# CE842170047_SHEET5.net
KiCad netlist of a schematic drawn in Altium Designer
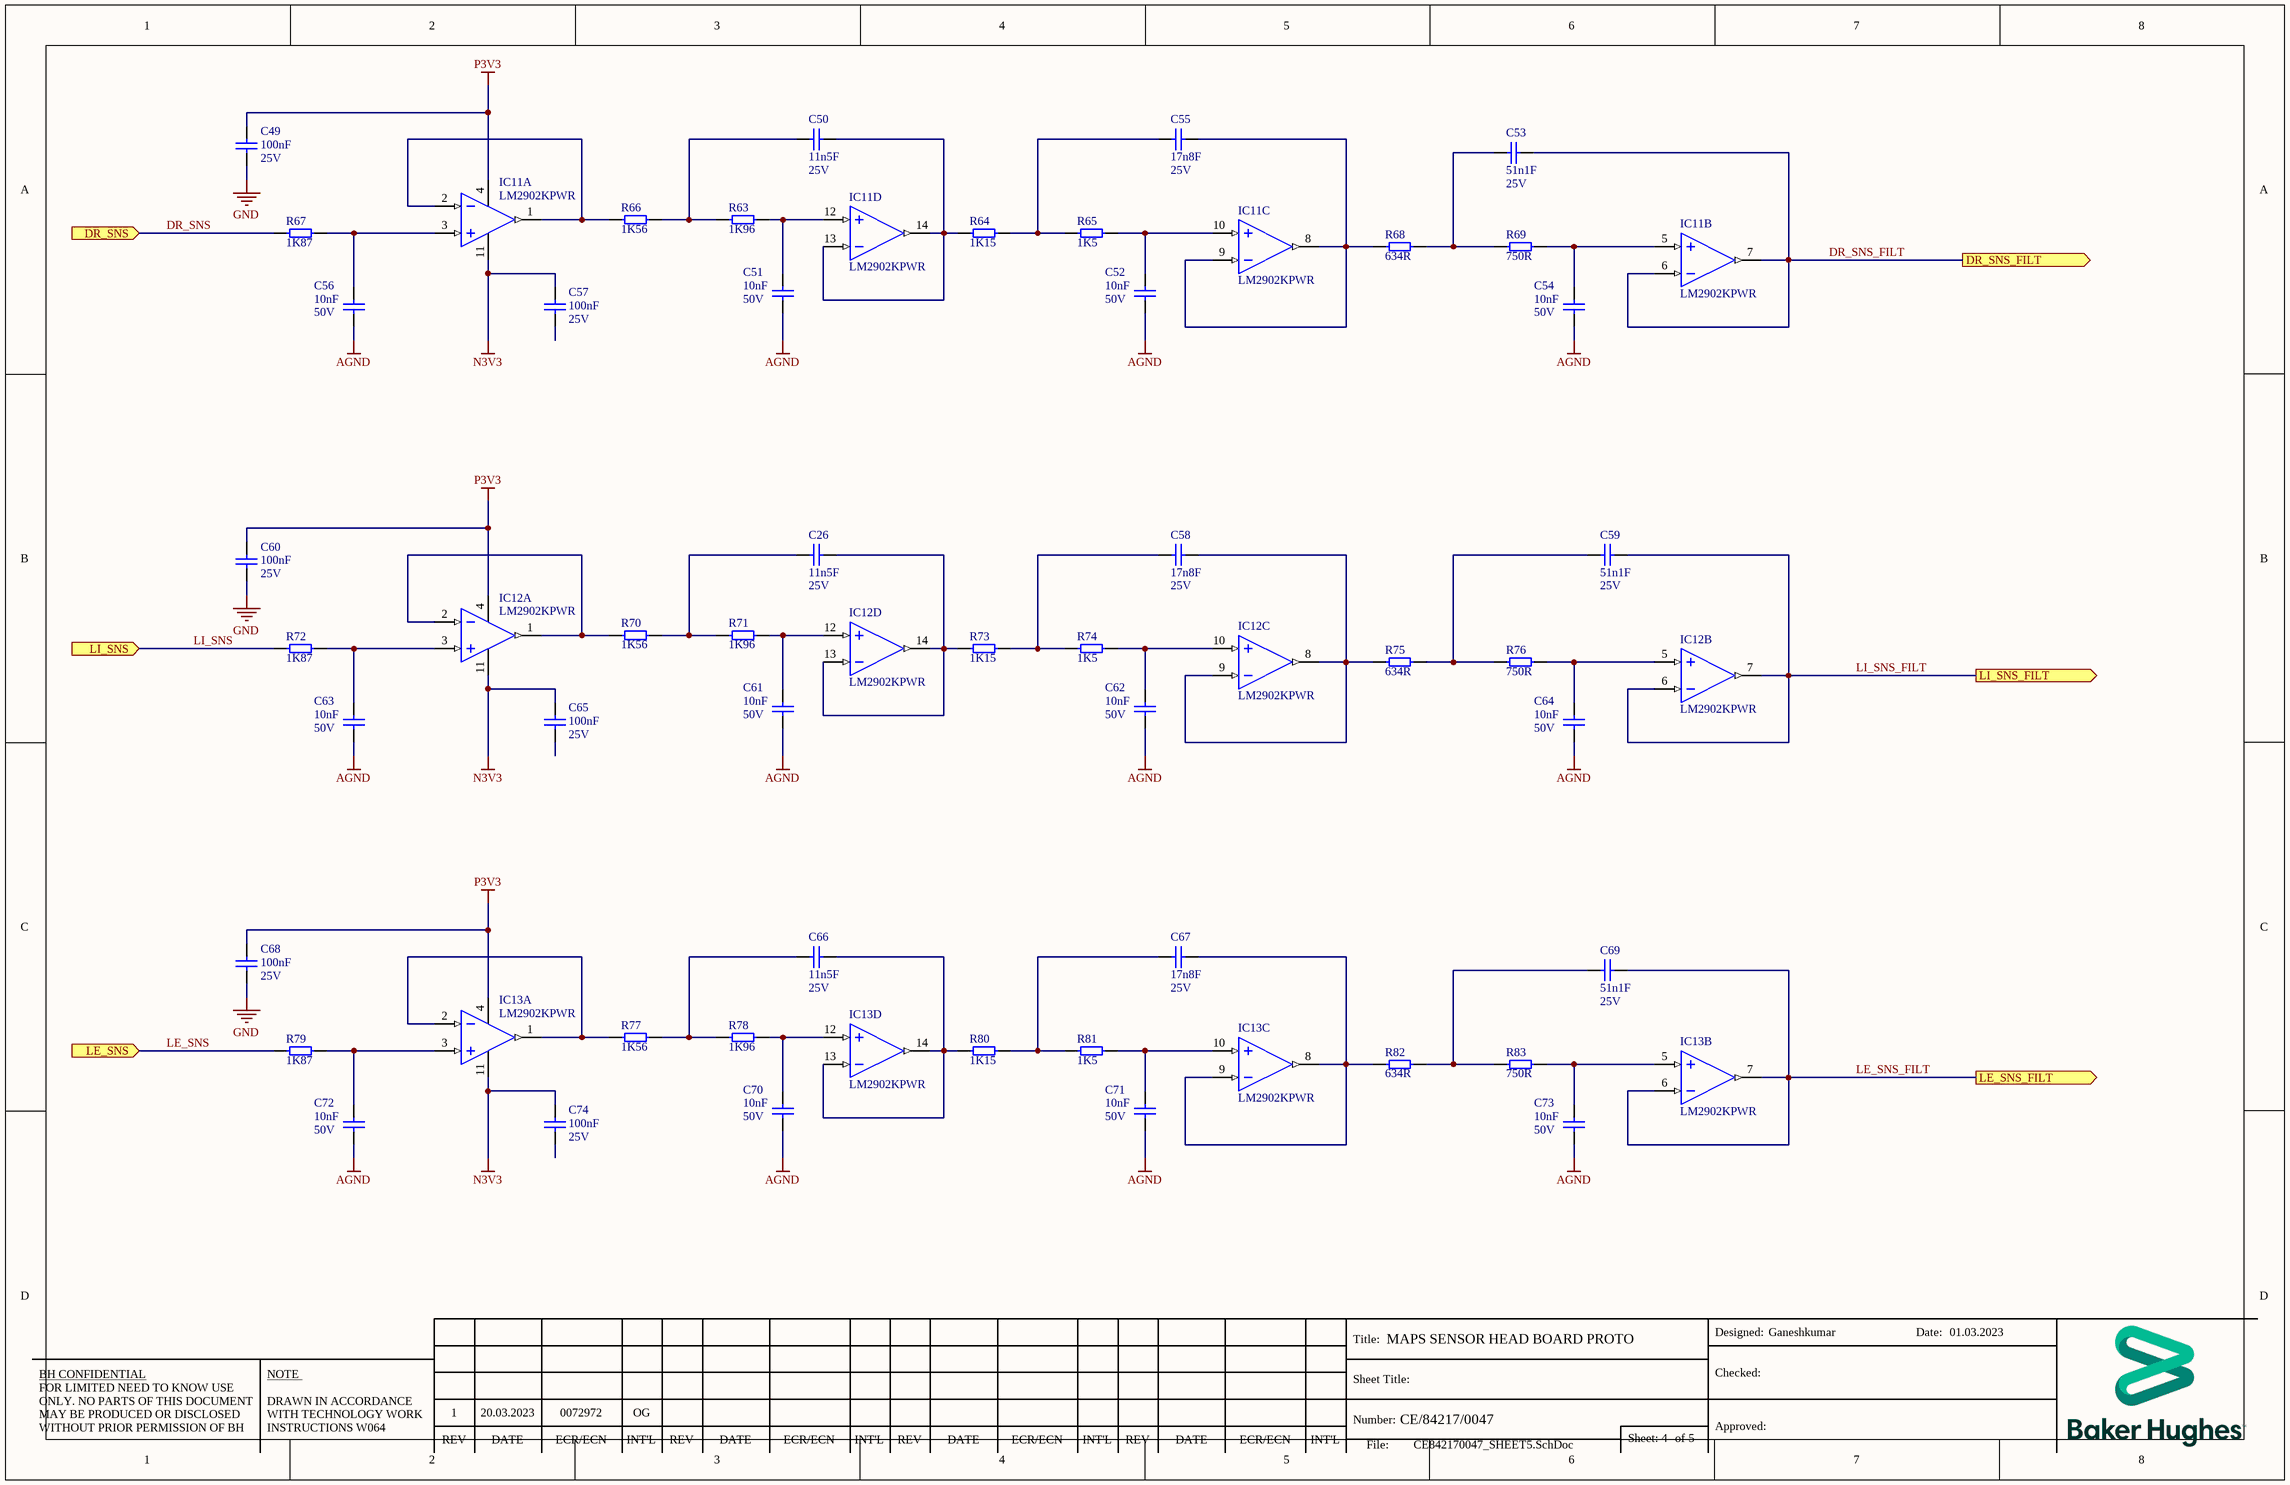
[diagram p0: CE842170047_SHEET5.SchDoc]

(export (version "E")
  (design (tool "Eeschema 10.0.6"))
  (components
    (comp (ref "C26")
      (value "11n5F")
      (footprint "C0603")
      (description "CAPACITOR CER 0603 11n5F 10% 25V X5R")
      (fields
        (field (name "VOLTAGE") "25V")
        (field (name "PII_PARTNUMBER") "KK/96159/0407")
        (field (name "TOLERANCE") "10%")
      )
      (libsource (lib "AltiumComponents") (part "CAP_GENERIC"))
    )
    (comp (ref "C49")
      (value "100nF")
      (footprint "C0603")
      (description "CAPACITOR_100nF_+10%_25V_603")
      (fields
        (field (name "VOLTAGE") "25V")
        (field (name "PII_PARTNUMBER") "KK/96159/4501")
        (field (name "TOLERANCE") "10%")
      )
      (libsource (lib "AltiumComponents") (part "CAP_GENERIC"))
    )
    (comp (ref "C50")
      (value "11n5F")
      (footprint "C0603")
      (description "CAPACITOR CER 0603 11n5F 10% 25V X5R")
      (fields
        (field (name "VOLTAGE") "25V")
        (field (name "PII_PARTNUMBER") "KK/96159/0407")
        (field (name "TOLERANCE") "10%")
      )
      (libsource (lib "AltiumComponents") (part "CAP_GENERIC"))
    )
    (comp (ref "C51")
      (value "10nF")
      (footprint "C0603")
      (description "CAPACITOR CERAMIC 0603 50V 10% X7R 10nF")
      (fields
        (field (name "VOLTAGE") "50V")
        (field (name "PII_PARTNUMBER") "KK/96159/0401")
        (field (name "TOLERANCE") "10%")
      )
      (libsource (lib "AltiumComponents") (part "CAP_GENERIC"))
    )
    (comp (ref "C52")
      (value "10nF")
      (footprint "C0603")
      (description "CAPACITOR CERAMIC 0603 50V 10% X7R 10nF")
      (fields
        (field (name "VOLTAGE") "50V")
        (field (name "PII_PARTNUMBER") "KK/96159/0401")
        (field (name "TOLERANCE") "10%")
      )
      (libsource (lib "AltiumComponents") (part "CAP_GENERIC"))
    )
    (comp (ref "C53")
      (value "51n1F")
      (footprint "C0603")
      (description "CAPACITOR CER 0603 51n1F 10% 25V X5R")
      (fields
        (field (name "VOLTAGE") "25V")
        (field (name "PII_PARTNUMBER") "KK/96159/0469")
        (field (name "TOLERANCE") "10%")
      )
      (libsource (lib "AltiumComponents") (part "CAP_GENERIC"))
    )
    (comp (ref "C54")
      (value "10nF")
      (footprint "C0603")
      (description "CAPACITOR CERAMIC 0603 50V 10% X7R 10nF")
      (fields
        (field (name "VOLTAGE") "50V")
        (field (name "PII_PARTNUMBER") "KK/96159/0401")
        (field (name "TOLERANCE") "10%")
      )
      (libsource (lib "AltiumComponents") (part "CAP_GENERIC"))
    )
    (comp (ref "C55")
      (value "17n8F")
      (footprint "C0603")
      (description "CAPACITOR CER 0603 17n8F 10% 25V X5R")
      (fields
        (field (name "VOLTAGE") "25V")
        (field (name "PII_PARTNUMBER") "KK/96159/0425")
        (field (name "TOLERANCE") "10%")
      )
      (libsource (lib "AltiumComponents") (part "CAP_GENERIC"))
    )
    (comp (ref "C56")
      (value "10nF")
      (footprint "C0603")
      (description "CAPACITOR CERAMIC 0603 50V 10% X7R 10nF")
      (fields
        (field (name "VOLTAGE") "50V")
        (field (name "PII_PARTNUMBER") "KK/96159/0401")
        (field (name "TOLERANCE") "10%")
      )
      (libsource (lib "AltiumComponents") (part "CAP_GENERIC"))
    )
    (comp (ref "C57")
      (value "100nF")
      (footprint "C0603")
      (description "CAPACITOR_100nF_+10%_25V_603")
      (fields
        (field (name "VOLTAGE") "25V")
        (field (name "PII_PARTNUMBER") "KK/96159/4501")
        (field (name "TOLERANCE") "10%")
      )
      (libsource (lib "AltiumComponents") (part "CAP_GENERIC"))
    )
    (comp (ref "C58")
      (value "17n8F")
      (footprint "C0603")
      (description "CAPACITOR CER 0603 17n8F 10% 25V X5R")
      (fields
        (field (name "VOLTAGE") "25V")
        (field (name "PII_PARTNUMBER") "KK/96159/0425")
        (field (name "TOLERANCE") "10%")
      )
      (libsource (lib "AltiumComponents") (part "CAP_GENERIC"))
    )
    (comp (ref "C59")
      (value "51n1F")
      (footprint "C0603")
      (description "CAPACITOR CER 0603 51n1F 10% 25V X5R")
      (fields
        (field (name "VOLTAGE") "25V")
        (field (name "PII_PARTNUMBER") "KK/96159/0469")
        (field (name "TOLERANCE") "10%")
      )
      (libsource (lib "AltiumComponents") (part "CAP_GENERIC"))
    )
    (comp (ref "C60")
      (value "100nF")
      (footprint "C0603")
      (description "CAPACITOR_100nF_+10%_25V_603")
      (fields
        (field (name "VOLTAGE") "25V")
        (field (name "PII_PARTNUMBER") "KK/96159/4501")
        (field (name "TOLERANCE") "10%")
      )
      (libsource (lib "AltiumComponents") (part "CAP_GENERIC"))
    )
    (comp (ref "C61")
      (value "10nF")
      (footprint "C0603")
      (description "CAPACITOR CERAMIC 0603 50V 10% X7R 10nF")
      (fields
        (field (name "VOLTAGE") "50V")
        (field (name "PII_PARTNUMBER") "KK/96159/0401")
        (field (name "TOLERANCE") "10%")
      )
      (libsource (lib "AltiumComponents") (part "CAP_GENERIC"))
    )
    (comp (ref "C62")
      (value "10nF")
      (footprint "C0603")
      (description "CAPACITOR CERAMIC 0603 50V 10% X7R 10nF")
      (fields
        (field (name "VOLTAGE") "50V")
        (field (name "PII_PARTNUMBER") "KK/96159/0401")
        (field (name "TOLERANCE") "10%")
      )
      (libsource (lib "AltiumComponents") (part "CAP_GENERIC"))
    )
    (comp (ref "C63")
      (value "10nF")
      (footprint "C0603")
      (description "CAPACITOR CERAMIC 0603 50V 10% X7R 10nF")
      (fields
        (field (name "VOLTAGE") "50V")
        (field (name "PII_PARTNUMBER") "KK/96159/0401")
        (field (name "TOLERANCE") "10%")
      )
      (libsource (lib "AltiumComponents") (part "CAP_GENERIC"))
    )
    (comp (ref "C64")
      (value "10nF")
      (footprint "C0603")
      (description "CAPACITOR CERAMIC 0603 50V 10% X7R 10nF")
      (fields
        (field (name "VOLTAGE") "50V")
        (field (name "PII_PARTNUMBER") "KK/96159/0401")
        (field (name "TOLERANCE") "10%")
      )
      (libsource (lib "AltiumComponents") (part "CAP_GENERIC"))
    )
    (comp (ref "C65")
      (value "100nF")
      (footprint "C0603")
      (description "CAPACITOR_100nF_+10%_25V_603")
      (fields
        (field (name "VOLTAGE") "25V")
        (field (name "PII_PARTNUMBER") "KK/96159/4501")
        (field (name "TOLERANCE") "10%")
      )
      (libsource (lib "AltiumComponents") (part "CAP_GENERIC"))
    )
    (comp (ref "C66")
      (value "11n5F")
      (footprint "C0603")
      (description "CAPACITOR CER 0603 11n5F 10% 25V X5R")
      (fields
        (field (name "VOLTAGE") "25V")
        (field (name "PII_PARTNUMBER") "KK/96159/0407")
        (field (name "TOLERANCE") "10%")
      )
      (libsource (lib "AltiumComponents") (part "CAP_GENERIC"))
    )
    (comp (ref "C67")
      (value "17n8F")
      (footprint "C0603")
      (description "CAPACITOR CER 0603 17n8F 10% 25V X5R")
      (fields
        (field (name "VOLTAGE") "25V")
        (field (name "PII_PARTNUMBER") "KK/96159/0425")
        (field (name "TOLERANCE") "10%")
      )
      (libsource (lib "AltiumComponents") (part "CAP_GENERIC"))
    )
    (comp (ref "C68")
      (value "100nF")
      (footprint "C0603")
      (description "CAPACITOR_100nF_+10%_25V_603")
      (fields
        (field (name "VOLTAGE") "25V")
        (field (name "PII_PARTNUMBER") "KK/96159/4501")
        (field (name "TOLERANCE") "10%")
      )
      (libsource (lib "AltiumComponents") (part "CAP_GENERIC"))
    )
    (comp (ref "C69")
      (value "51n1F")
      (footprint "C0603")
      (description "CAPACITOR CER 0603 51n1F 10% 25V X5R")
      (fields
        (field (name "VOLTAGE") "25V")
        (field (name "PII_PARTNUMBER") "KK/96159/0469")
        (field (name "TOLERANCE") "10%")
      )
      (libsource (lib "AltiumComponents") (part "CAP_GENERIC"))
    )
    (comp (ref "C70")
      (value "10nF")
      (footprint "C0603")
      (description "CAPACITOR CERAMIC 0603 50V 10% X7R 10nF")
      (fields
        (field (name "VOLTAGE") "50V")
        (field (name "PII_PARTNUMBER") "KK/96159/0401")
        (field (name "TOLERANCE") "10%")
      )
      (libsource (lib "AltiumComponents") (part "CAP_GENERIC"))
    )
    (comp (ref "C71")
      (value "10nF")
      (footprint "C0603")
      (description "CAPACITOR CERAMIC 0603 50V 10% X7R 10nF")
      (fields
        (field (name "VOLTAGE") "50V")
        (field (name "PII_PARTNUMBER") "KK/96159/0401")
        (field (name "TOLERANCE") "10%")
      )
      (libsource (lib "AltiumComponents") (part "CAP_GENERIC"))
    )
    (comp (ref "C72")
      (value "10nF")
      (footprint "C0603")
      (description "CAPACITOR CERAMIC 0603 50V 10% X7R 10nF")
      (fields
        (field (name "VOLTAGE") "50V")
        (field (name "PII_PARTNUMBER") "KK/96159/0401")
        (field (name "TOLERANCE") "10%")
      )
      (libsource (lib "AltiumComponents") (part "CAP_GENERIC"))
    )
    (comp (ref "C73")
      (value "10nF")
      (footprint "C0603")
      (description "CAPACITOR CERAMIC 0603 50V 10% X7R 10nF")
      (fields
        (field (name "VOLTAGE") "50V")
        (field (name "PII_PARTNUMBER") "KK/96159/0401")
        (field (name "TOLERANCE") "10%")
      )
      (libsource (lib "AltiumComponents") (part "CAP_GENERIC"))
    )
    (comp (ref "C74")
      (value "100nF")
      (footprint "C0603")
      (description "CAPACITOR_100nF_+10%_25V_603")
      (fields
        (field (name "VOLTAGE") "25V")
        (field (name "PII_PARTNUMBER") "KK/96159/4501")
        (field (name "TOLERANCE") "10%")
      )
      (libsource (lib "AltiumComponents") (part "CAP_GENERIC"))
    )
    (comp (ref "IC11")
      (value "LM2902")
      (footprint "TSSOP-14")
      (description "IC,QUAD OP.AMP,TSSOP-14,ST,LM2902KPWR")
      (fields
        (field (name "MF_PARTNUMBER") "LM2902KPWR")
        (field (name "PII_PARTNUMBER") "KK/95300/0171")
        (field (name "VOLTAGE") "3V to 32V")
      )
      (libsource (lib "AltiumComponents") (part "LM2902"))
    )
    (comp (ref "IC12")
      (value "LM2902")
      (footprint "TSSOP-14")
      (description "IC,QUAD OP.AMP,TSSOP-14,ST,LM2902KPWR")
      (fields
        (field (name "MF_PARTNUMBER") "LM2902KPWR")
        (field (name "PII_PARTNUMBER") "KK/95300/0171")
        (field (name "VOLTAGE") "3V to 32V")
      )
      (libsource (lib "AltiumComponents") (part "LM2902"))
    )
    (comp (ref "IC13")
      (value "LM2902")
      (footprint "TSSOP-14")
      (description "IC,QUAD OP.AMP,TSSOP-14,ST,LM2902KPWR")
      (fields
        (field (name "MF_PARTNUMBER") "LM2902KPWR")
        (field (name "PII_PARTNUMBER") "KK/95300/0171")
        (field (name "VOLTAGE") "3V to 32V")
      )
      (libsource (lib "AltiumComponents") (part "LM2902"))
    )
    (comp (ref "R63")
      (value "1K96")
      (footprint "R0603")
      (description "RESISTOR 0603 0.063W 1% 1K96")
      (fields (field (name "PII_PARTNUMBER") "KK/96059/0529") (field (name "TOLERANCE") "1%"))
      (libsource (lib "AltiumComponents") (part "RES_GENERIC"))
    )
    (comp (ref "R64")
      (value "1K15")
      (footprint "R0603")
      (description "RESISTOR 0603 0.063W 1% 1K15")
      (fields (field (name "PII_PARTNUMBER") "KK/96059/0507") (field (name "TOLERANCE") "1%"))
      (libsource (lib "AltiumComponents") (part "RES_GENERIC"))
    )
    (comp (ref "R65")
      (value "1K5")
      (footprint "R0603")
      (description "RESISTOR 0603 0.1W 1% 1K5")
      (fields (field (name "PII_PARTNUMBER") "KK/96059/0518") (field (name "TOLERANCE") "1%"))
      (libsource (lib "AltiumComponents") (part "RES_GENERIC"))
    )
    (comp (ref "R66")
      (value "1K56")
      (footprint "R0603")
      (description "RESISTOR 0603 0.063W 1% 1K56")
      (fields (field (name "PII_PARTNUMBER") "KK/96059/0519") (field (name "TOLERANCE") "1%"))
      (libsource (lib "AltiumComponents") (part "RES_GENERIC"))
    )
    (comp (ref "R67")
      (value "1K87")
      (footprint "R0603")
      (description "RESISTOR 0603 0.063W 1% 1K87")
      (fields (field (name "PII_PARTNUMBER") "KK/96059/0527") (field (name "TOLERANCE") "1%"))
      (libsource (lib "AltiumComponents") (part "RES_GENERIC"))
    )
    (comp (ref "R68")
      (value "634R")
      (footprint "R0603")
      (description "RESISTOR 0603 0.063W 1% 634R")
      (fields (field (name "PII_PARTNUMBER") "KK/96059/0478") (field (name "TOLERANCE") "1%"))
      (libsource (lib "AltiumComponents") (part "RES_GENERIC"))
    )
    (comp (ref "R69")
      (value "750R")
      (footprint "R0603")
      (description "RESISTOR 0603 0.063W 1% 750R")
      (fields (field (name "PII_PARTNUMBER") "KK/96059/0485") (field (name "TOLERANCE") "1%"))
      (libsource (lib "AltiumComponents") (part "RES_GENERIC"))
    )
    (comp (ref "R70")
      (value "1K56")
      (footprint "R0603")
      (description "RESISTOR 0603 0.063W 1% 1K56")
      (fields (field (name "PII_PARTNUMBER") "KK/96059/0519") (field (name "TOLERANCE") "1%"))
      (libsource (lib "AltiumComponents") (part "RES_GENERIC"))
    )
    (comp (ref "R71")
      (value "1K96")
      (footprint "R0603")
      (description "RESISTOR 0603 0.063W 1% 1K96")
      (fields (field (name "PII_PARTNUMBER") "KK/96059/0529") (field (name "TOLERANCE") "1%"))
      (libsource (lib "AltiumComponents") (part "RES_GENERIC"))
    )
    (comp (ref "R72")
      (value "1K87")
      (footprint "R0603")
      (description "RESISTOR 0603 0.063W 1% 1K87")
      (fields (field (name "PII_PARTNUMBER") "KK/96059/0527") (field (name "TOLERANCE") "1%"))
      (libsource (lib "AltiumComponents") (part "RES_GENERIC"))
    )
    (comp (ref "R73")
      (value "1K15")
      (footprint "R0603")
      (description "RESISTOR 0603 0.063W 1% 1K15")
      (fields (field (name "PII_PARTNUMBER") "KK/96059/0507") (field (name "TOLERANCE") "1%"))
      (libsource (lib "AltiumComponents") (part "RES_GENERIC"))
    )
    (comp (ref "R74")
      (value "1K5")
      (footprint "R0603")
      (description "RESISTOR 0603 0.1W 1% 1K5")
      (fields (field (name "PII_PARTNUMBER") "KK/96059/0518") (field (name "TOLERANCE") "1%"))
      (libsource (lib "AltiumComponents") (part "RES_GENERIC"))
    )
    (comp (ref "R75")
      (value "634R")
      (footprint "R0603")
      (description "RESISTOR 0603 0.063W 1% 634R")
      (fields (field (name "PII_PARTNUMBER") "KK/96059/0478") (field (name "TOLERANCE") "1%"))
      (libsource (lib "AltiumComponents") (part "RES_GENERIC"))
    )
    (comp (ref "R76")
      (value "750R")
      (footprint "R0603")
      (description "RESISTOR 0603 0.063W 1% 750R")
      (fields (field (name "PII_PARTNUMBER") "KK/96059/0485") (field (name "TOLERANCE") "1%"))
      (libsource (lib "AltiumComponents") (part "RES_GENERIC"))
    )
    (comp (ref "R77")
      (value "1K56")
      (footprint "R0603")
      (description "RESISTOR 0603 0.063W 1% 1K56")
      (fields (field (name "PII_PARTNUMBER") "KK/96059/0519") (field (name "TOLERANCE") "1%"))
      (libsource (lib "AltiumComponents") (part "RES_GENERIC"))
    )
    (comp (ref "R78")
      (value "1K96")
      (footprint "R0603")
      (description "RESISTOR 0603 0.063W 1% 1K96")
      (fields (field (name "PII_PARTNUMBER") "KK/96059/0529") (field (name "TOLERANCE") "1%"))
      (libsource (lib "AltiumComponents") (part "RES_GENERIC"))
    )
    (comp (ref "R79")
      (value "1K87")
      (footprint "R0603")
      (description "RESISTOR 0603 0.063W 1% 1K87")
      (fields (field (name "PII_PARTNUMBER") "KK/96059/0527") (field (name "TOLERANCE") "1%"))
      (libsource (lib "AltiumComponents") (part "RES_GENERIC"))
    )
    (comp (ref "R80")
      (value "1K15")
      (footprint "R0603")
      (description "RESISTOR 0603 0.063W 1% 1K15")
      (fields (field (name "PII_PARTNUMBER") "KK/96059/0507") (field (name "TOLERANCE") "1%"))
      (libsource (lib "AltiumComponents") (part "RES_GENERIC"))
    )
    (comp (ref "R81")
      (value "1K5")
      (footprint "R0603")
      (description "RESISTOR 0603 0.1W 1% 1K5")
      (fields (field (name "PII_PARTNUMBER") "KK/96059/0518") (field (name "TOLERANCE") "1%"))
      (libsource (lib "AltiumComponents") (part "RES_GENERIC"))
    )
    (comp (ref "R82")
      (value "634R")
      (footprint "R0603")
      (description "RESISTOR 0603 0.063W 1% 634R")
      (fields (field (name "PII_PARTNUMBER") "KK/96059/0478") (field (name "TOLERANCE") "1%"))
      (libsource (lib "AltiumComponents") (part "RES_GENERIC"))
    )
    (comp (ref "R83")
      (value "750R")
      (footprint "R0603")
      (description "RESISTOR 0603 0.063W 1% 750R")
      (fields (field (name "PII_PARTNUMBER") "KK/96059/0485") (field (name "TOLERANCE") "1%"))
      (libsource (lib "AltiumComponents") (part "RES_GENERIC"))
    )
  )
  (nets
    (net (code "1") (name "/DR_SNS") (class "Default")
      (node (ref "R67") (pin "1") (pinfunction "1_1") (pintype "passive"))
    )
    (net (code "2") (name "/DR_SNS_FILT") (class "Default")
      (node (ref "C53") (pin "1") (pinfunction "1_1") (pintype "passive"))
      (node (ref "IC11") (pin "6") (pinfunction "2IN-_6") (pintype "input"))
      (node (ref "IC11") (pin "7") (pinfunction "2OUT_7") (pintype "output"))
    )
    (net (code "3") (name "/LE_SNS") (class "Default")
      (node (ref "R79") (pin "1") (pinfunction "1_1") (pintype "passive"))
    )
    (net (code "4") (name "/LE_SNS_FILT") (class "Default")
      (node (ref "C69") (pin "1") (pinfunction "1_1") (pintype "passive"))
      (node (ref "IC13") (pin "6") (pinfunction "2IN-_6") (pintype "input"))
      (node (ref "IC13") (pin "7") (pinfunction "2OUT_7") (pintype "output"))
    )
    (net (code "5") (name "/LI_SNS") (class "Default")
      (node (ref "R72") (pin "1") (pinfunction "1_1") (pintype "passive"))
    )
    (net (code "6") (name "/LI_SNS_FILT") (class "Default")
      (node (ref "C59") (pin "1") (pinfunction "1_1") (pintype "passive"))
      (node (ref "IC12") (pin "6") (pinfunction "2IN-_6") (pintype "input"))
      (node (ref "IC12") (pin "7") (pinfunction "2OUT_7") (pintype "output"))
    )
    (net (code "7") (name "AGND") (class "Default")
      (node (ref "C51") (pin "2") (pinfunction "2_2") (pintype "passive"))
      (node (ref "C52") (pin "2") (pinfunction "2_2") (pintype "passive"))
      (node (ref "C54") (pin "2") (pinfunction "2_2") (pintype "passive"))
      (node (ref "C56") (pin "2") (pinfunction "2_2") (pintype "passive"))
      (node (ref "C61") (pin "2") (pinfunction "2_2") (pintype "passive"))
      (node (ref "C62") (pin "2") (pinfunction "2_2") (pintype "passive"))
      (node (ref "C63") (pin "2") (pinfunction "2_2") (pintype "passive"))
      (node (ref "C64") (pin "2") (pinfunction "2_2") (pintype "passive"))
      (node (ref "C70") (pin "2") (pinfunction "2_2") (pintype "passive"))
      (node (ref "C71") (pin "2") (pinfunction "2_2") (pintype "passive"))
      (node (ref "C72") (pin "2") (pinfunction "2_2") (pintype "passive"))
      (node (ref "C73") (pin "2") (pinfunction "2_2") (pintype "passive"))
    )
    (net (code "8") (name "GND") (class "Default")
      (node (ref "C49") (pin "2") (pinfunction "2_2") (pintype "passive"))
      (node (ref "C60") (pin "2") (pinfunction "2_2") (pintype "passive"))
      (node (ref "C68") (pin "2") (pinfunction "2_2") (pintype "passive"))
    )
    (net (code "9") (name "N3V3") (class "Default")
      (node (ref "C57") (pin "1") (pinfunction "1_1") (pintype "passive"))
      (node (ref "C65") (pin "1") (pinfunction "1_1") (pintype "passive"))
      (node (ref "C74") (pin "1") (pinfunction "1_1") (pintype "passive"))
      (node (ref "IC11") (pin "11") (pinfunction "GND_11") (pintype "power_in"))
      (node (ref "IC12") (pin "11") (pinfunction "GND_11") (pintype "power_in"))
      (node (ref "IC13") (pin "11") (pinfunction "GND_11") (pintype "power_in"))
    )
    (net (code "10") (name "Net-(C26-Pad1)") (class "Default")
      (node (ref "C26") (pin "1") (pinfunction "1_1") (pintype "passive"))
      (node (ref "R70") (pin "2") (pinfunction "2_2") (pintype "passive"))
      (node (ref "R71") (pin "1") (pinfunction "1_1") (pintype "passive"))
    )
    (net (code "11") (name "Net-(C50-Pad1)") (class "Default")
      (node (ref "C50") (pin "1") (pinfunction "1_1") (pintype "passive"))
      (node (ref "R63") (pin "1") (pinfunction "1_1") (pintype "passive"))
      (node (ref "R66") (pin "2") (pinfunction "2_2") (pintype "passive"))
    )
    (net (code "12") (name "Net-(C53-Pad2)") (class "Default")
      (node (ref "C53") (pin "2") (pinfunction "2_2") (pintype "passive"))
      (node (ref "R68") (pin "2") (pinfunction "2_2") (pintype "passive"))
      (node (ref "R69") (pin "1") (pinfunction "1_1") (pintype "passive"))
    )
    (net (code "13") (name "Net-(C55-Pad1)") (class "Default")
      (node (ref "C55") (pin "1") (pinfunction "1_1") (pintype "passive"))
      (node (ref "R64") (pin "2") (pinfunction "2_2") (pintype "passive"))
      (node (ref "R65") (pin "1") (pinfunction "1_1") (pintype "passive"))
    )
    (net (code "14") (name "Net-(C58-Pad1)") (class "Default")
      (node (ref "C58") (pin "1") (pinfunction "1_1") (pintype "passive"))
      (node (ref "R73") (pin "2") (pinfunction "2_2") (pintype "passive"))
      (node (ref "R74") (pin "1") (pinfunction "1_1") (pintype "passive"))
    )
    (net (code "15") (name "Net-(C59-Pad2)") (class "Default")
      (node (ref "C59") (pin "2") (pinfunction "2_2") (pintype "passive"))
      (node (ref "R75") (pin "2") (pinfunction "2_2") (pintype "passive"))
      (node (ref "R76") (pin "1") (pinfunction "1_1") (pintype "passive"))
    )
    (net (code "16") (name "Net-(C66-Pad1)") (class "Default")
      (node (ref "C66") (pin "1") (pinfunction "1_1") (pintype "passive"))
      (node (ref "R77") (pin "2") (pinfunction "2_2") (pintype "passive"))
      (node (ref "R78") (pin "1") (pinfunction "1_1") (pintype "passive"))
    )
    (net (code "17") (name "Net-(C67-Pad1)") (class "Default")
      (node (ref "C67") (pin "1") (pinfunction "1_1") (pintype "passive"))
      (node (ref "R80") (pin "2") (pinfunction "2_2") (pintype "passive"))
      (node (ref "R81") (pin "1") (pinfunction "1_1") (pintype "passive"))
    )
    (net (code "18") (name "Net-(C69-Pad2)") (class "Default")
      (node (ref "C69") (pin "2") (pinfunction "2_2") (pintype "passive"))
      (node (ref "R82") (pin "2") (pinfunction "2_2") (pintype "passive"))
      (node (ref "R83") (pin "1") (pinfunction "1_1") (pintype "passive"))
    )
    (net (code "19") (name "Net-(IC11A-1IN+)") (class "Default")
      (node (ref "C56") (pin "1") (pinfunction "1_1") (pintype "passive"))
      (node (ref "IC11") (pin "3") (pinfunction "1IN+_3") (pintype "input"))
      (node (ref "R67") (pin "2") (pinfunction "2_2") (pintype "passive"))
    )
    (net (code "20") (name "Net-(IC11A-1IN-)") (class "Default")
      (node (ref "IC11") (pin "1") (pinfunction "1OUT_1") (pintype "output"))
      (node (ref "IC11") (pin "2") (pinfunction "1IN-_2") (pintype "input"))
      (node (ref "R66") (pin "1") (pinfunction "1_1") (pintype "passive"))
    )
    (net (code "21") (name "Net-(IC11B-2IN+)") (class "Default")
      (node (ref "C54") (pin "1") (pinfunction "1_1") (pintype "passive"))
      (node (ref "IC11") (pin "5") (pinfunction "2IN+_5") (pintype "input"))
      (node (ref "R69") (pin "2") (pinfunction "2_2") (pintype "passive"))
    )
    (net (code "22") (name "Net-(IC11C-3IN+)") (class "Default")
      (node (ref "C52") (pin "1") (pinfunction "1_1") (pintype "passive"))
      (node (ref "IC11") (pin "10") (pinfunction "3IN+_10") (pintype "input"))
      (node (ref "R65") (pin "2") (pinfunction "2_2") (pintype "passive"))
    )
    (net (code "23") (name "Net-(IC11C-3IN-)") (class "Default")
      (node (ref "C55") (pin "2") (pinfunction "2_2") (pintype "passive"))
      (node (ref "IC11") (pin "8") (pinfunction "3OUT_8") (pintype "output"))
      (node (ref "IC11") (pin "9") (pinfunction "3IN-_9") (pintype "input"))
      (node (ref "R68") (pin "1") (pinfunction "1_1") (pintype "passive"))
    )
    (net (code "24") (name "Net-(IC11D-4IN+)") (class "Default")
      (node (ref "C51") (pin "1") (pinfunction "1_1") (pintype "passive"))
      (node (ref "IC11") (pin "12") (pinfunction "4IN+_12") (pintype "input"))
      (node (ref "R63") (pin "2") (pinfunction "2_2") (pintype "passive"))
    )
    (net (code "25") (name "Net-(IC11D-4IN-)") (class "Default")
      (node (ref "C50") (pin "2") (pinfunction "2_2") (pintype "passive"))
      (node (ref "IC11") (pin "13") (pinfunction "4IN-_13") (pintype "input"))
      (node (ref "IC11") (pin "14") (pinfunction "4OUT_14") (pintype "output"))
      (node (ref "R64") (pin "1") (pinfunction "1_1") (pintype "passive"))
    )
    (net (code "26") (name "Net-(IC12A-1IN+)") (class "Default")
      (node (ref "C63") (pin "1") (pinfunction "1_1") (pintype "passive"))
      (node (ref "IC12") (pin "3") (pinfunction "1IN+_3") (pintype "input"))
      (node (ref "R72") (pin "2") (pinfunction "2_2") (pintype "passive"))
    )
    (net (code "27") (name "Net-(IC12A-1IN-)") (class "Default")
      (node (ref "IC12") (pin "1") (pinfunction "1OUT_1") (pintype "output"))
      (node (ref "IC12") (pin "2") (pinfunction "1IN-_2") (pintype "input"))
      (node (ref "R70") (pin "1") (pinfunction "1_1") (pintype "passive"))
    )
    (net (code "28") (name "Net-(IC12B-2IN+)") (class "Default")
      (node (ref "C64") (pin "1") (pinfunction "1_1") (pintype "passive"))
      (node (ref "IC12") (pin "5") (pinfunction "2IN+_5") (pintype "input"))
      (node (ref "R76") (pin "2") (pinfunction "2_2") (pintype "passive"))
    )
    (net (code "29") (name "Net-(IC12C-3IN+)") (class "Default")
      (node (ref "C62") (pin "1") (pinfunction "1_1") (pintype "passive"))
      (node (ref "IC12") (pin "10") (pinfunction "3IN+_10") (pintype "input"))
      (node (ref "R74") (pin "2") (pinfunction "2_2") (pintype "passive"))
    )
    (net (code "30") (name "Net-(IC12C-3IN-)") (class "Default")
      (node (ref "C58") (pin "2") (pinfunction "2_2") (pintype "passive"))
      (node (ref "IC12") (pin "8") (pinfunction "3OUT_8") (pintype "output"))
      (node (ref "IC12") (pin "9") (pinfunction "3IN-_9") (pintype "input"))
      (node (ref "R75") (pin "1") (pinfunction "1_1") (pintype "passive"))
    )
    (net (code "31") (name "Net-(IC12D-4IN+)") (class "Default")
      (node (ref "C61") (pin "1") (pinfunction "1_1") (pintype "passive"))
      (node (ref "IC12") (pin "12") (pinfunction "4IN+_12") (pintype "input"))
      (node (ref "R71") (pin "2") (pinfunction "2_2") (pintype "passive"))
    )
    (net (code "32") (name "Net-(IC12D-4IN-)") (class "Default")
      (node (ref "C26") (pin "2") (pinfunction "2_2") (pintype "passive"))
      (node (ref "IC12") (pin "13") (pinfunction "4IN-_13") (pintype "input"))
      (node (ref "IC12") (pin "14") (pinfunction "4OUT_14") (pintype "output"))
      (node (ref "R73") (pin "1") (pinfunction "1_1") (pintype "passive"))
    )
    (net (code "33") (name "Net-(IC13A-1IN+)") (class "Default")
      (node (ref "C72") (pin "1") (pinfunction "1_1") (pintype "passive"))
      (node (ref "IC13") (pin "3") (pinfunction "1IN+_3") (pintype "input"))
      (node (ref "R79") (pin "2") (pinfunction "2_2") (pintype "passive"))
    )
    (net (code "34") (name "Net-(IC13A-1IN-)") (class "Default")
      (node (ref "IC13") (pin "1") (pinfunction "1OUT_1") (pintype "output"))
      (node (ref "IC13") (pin "2") (pinfunction "1IN-_2") (pintype "input"))
      (node (ref "R77") (pin "1") (pinfunction "1_1") (pintype "passive"))
    )
    (net (code "35") (name "Net-(IC13B-2IN+)") (class "Default")
      (node (ref "C73") (pin "1") (pinfunction "1_1") (pintype "passive"))
      (node (ref "IC13") (pin "5") (pinfunction "2IN+_5") (pintype "input"))
      (node (ref "R83") (pin "2") (pinfunction "2_2") (pintype "passive"))
    )
    (net (code "36") (name "Net-(IC13C-3IN+)") (class "Default")
      (node (ref "C71") (pin "1") (pinfunction "1_1") (pintype "passive"))
      (node (ref "IC13") (pin "10") (pinfunction "3IN+_10") (pintype "input"))
      (node (ref "R81") (pin "2") (pinfunction "2_2") (pintype "passive"))
    )
    (net (code "37") (name "Net-(IC13C-3IN-)") (class "Default")
      (node (ref "C67") (pin "2") (pinfunction "2_2") (pintype "passive"))
      (node (ref "IC13") (pin "8") (pinfunction "3OUT_8") (pintype "output"))
      (node (ref "IC13") (pin "9") (pinfunction "3IN-_9") (pintype "input"))
      (node (ref "R82") (pin "1") (pinfunction "1_1") (pintype "passive"))
    )
    (net (code "38") (name "Net-(IC13D-4IN+)") (class "Default")
      (node (ref "C70") (pin "1") (pinfunction "1_1") (pintype "passive"))
      (node (ref "IC13") (pin "12") (pinfunction "4IN+_12") (pintype "input"))
      (node (ref "R78") (pin "2") (pinfunction "2_2") (pintype "passive"))
    )
    (net (code "39") (name "Net-(IC13D-4IN-)") (class "Default")
      (node (ref "C66") (pin "2") (pinfunction "2_2") (pintype "passive"))
      (node (ref "IC13") (pin "13") (pinfunction "4IN-_13") (pintype "input"))
      (node (ref "IC13") (pin "14") (pinfunction "4OUT_14") (pintype "output"))
      (node (ref "R80") (pin "1") (pinfunction "1_1") (pintype "passive"))
    )
    (net (code "40") (name "P3V3") (class "Default")
      (node (ref "C49") (pin "1") (pinfunction "1_1") (pintype "passive"))
      (node (ref "C60") (pin "1") (pinfunction "1_1") (pintype "passive"))
      (node (ref "C68") (pin "1") (pinfunction "1_1") (pintype "passive"))
      (node (ref "IC11") (pin "4") (pinfunction "VCC_4") (pintype "power_in"))
      (node (ref "IC12") (pin "4") (pinfunction "VCC_4") (pintype "power_in"))
      (node (ref "IC13") (pin "4") (pinfunction "VCC_4") (pintype "power_in"))
    )
    (net (code "41") (name "unconnected-(C57-Pad2)") (class "Default")
      (node (ref "C57") (pin "2") (pinfunction "2_2") (pintype "passive"))
    )
    (net (code "42") (name "unconnected-(C65-Pad2)") (class "Default")
      (node (ref "C65") (pin "2") (pinfunction "2_2") (pintype "passive"))
    )
    (net (code "43") (name "unconnected-(C74-Pad2)") (class "Default")
      (node (ref "C74") (pin "2") (pinfunction "2_2") (pintype "passive"))
    )
  )
)
